# Sheet2.net
KiCad netlist of a schematic drawn in Altium Designer
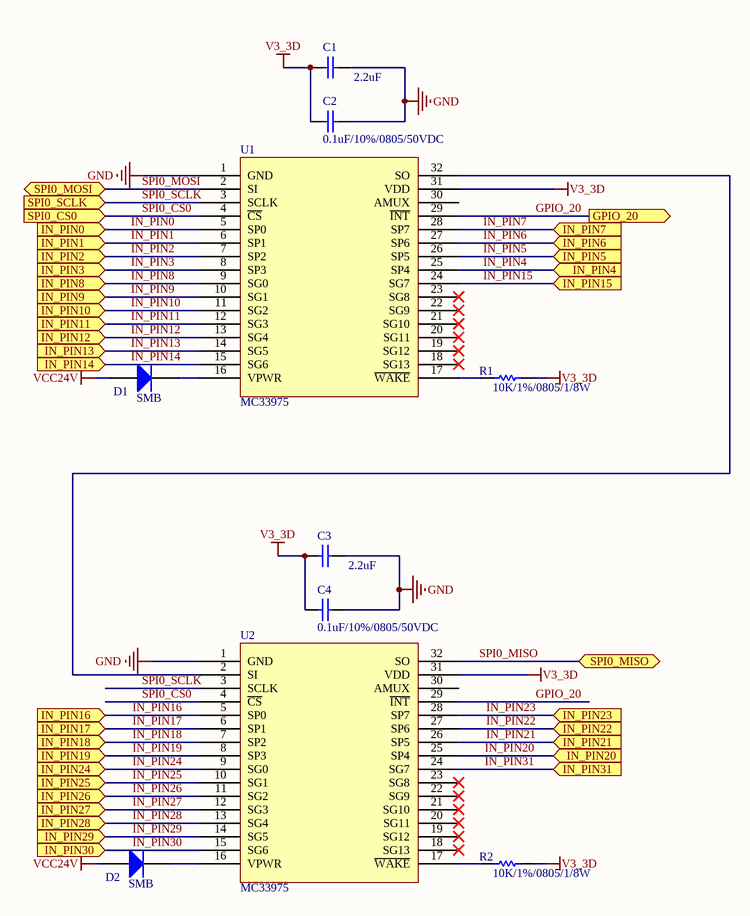
[diagram p0: Sheet2.SchDoc]

(export (version "E")
  (design (tool "Eeschema 10.0.6"))
  (components
    (comp (ref "C1")
      (value "2.2uF")
      (footprint "0805_cap")
      (description "Capacitor")
      (fields (field (name "PUBLISHER") "Altium Limited"))
      (libsource (lib "Miscellaneous Devices") (part "Cap"))
    )
    (comp (ref "C2")
      (value "0.1uF/10%/0805/50VDC")
      (footprint "0805_cap")
      (libsource (lib "浙江关西电机数据库") (part "CAP_Non-polarity"))
    )
    (comp (ref "C3")
      (value "2.2uF")
      (footprint "0805_cap")
      (description "Capacitor")
      (fields (field (name "PUBLISHER") "Altium Limited"))
      (libsource (lib "Miscellaneous Devices") (part "Cap"))
    )
    (comp (ref "C4")
      (value "0.1uF/10%/0805/50VDC")
      (footprint "0805_cap")
      (libsource (lib "浙江关西电机数据库") (part "CAP_Non-polarity"))
    )
    (comp (ref "D1")
      (value "SMB")
      (footprint "SMB")
      (description "3 Amp Medium Power Silicon Rectifier Diode")
      (fields (field (name "PUBLISHER") "Altium Limited"))
      (libsource (lib "Miscellaneous Devices") (part "Diode 1N5408"))
    )
    (comp (ref "D2")
      (value "SMB")
      (footprint "SMB")
      (description "3 Amp Medium Power Silicon Rectifier Diode")
      (fields (field (name "PUBLISHER") "Altium Limited"))
      (libsource (lib "Miscellaneous Devices") (part "Diode 1N5408"))
    )
    (comp (ref "R1")
      (value "10K/1%/0805/1/8W")
      (footprint "0805")
      (fields (field (name "PART NUMBER") "ASR-0028BA"))
      (libsource (lib "浙江关西电机数据库") (part "RES_1"))
    )
    (comp (ref "R2")
      (value "10K/1%/0805/1/8W")
      (footprint "0805")
      (fields (field (name "PART NUMBER") "ASR-0028BA"))
      (libsource (lib "浙江关西电机数据库") (part "RES_1"))
    )
    (comp (ref "U1")
      (value "MC33975")
      (footprint "SOIC-32")
      (libsource (lib "SCHLIBRARIES") (part "MC33975"))
    )
    (comp (ref "U2")
      (value "MC33975")
      (footprint "SOIC-32")
      (libsource (lib "SCHLIBRARIES") (part "MC33975"))
    )
  )
  (nets
    (net (code "1") (name "/GPIO_20") (class "Default")
      (node (ref "U1") (pin "29") (pinfunction "~{INT}_29") (pintype "passive"))
      (node (ref "U2") (pin "29") (pinfunction "~{INT}_29") (pintype "passive"))
    )
    (net (code "2") (name "/IN_PIN0") (class "Default")
      (node (ref "U1") (pin "5") (pinfunction "SP0_5") (pintype "passive"))
    )
    (net (code "3") (name "/IN_PIN1") (class "Default")
      (node (ref "U1") (pin "6") (pinfunction "SP1_6") (pintype "passive"))
    )
    (net (code "4") (name "/IN_PIN2") (class "Default")
      (node (ref "U1") (pin "7") (pinfunction "SP2_7") (pintype "passive"))
    )
    (net (code "5") (name "/IN_PIN3") (class "Default")
      (node (ref "U1") (pin "8") (pinfunction "SP3_8") (pintype "passive"))
    )
    (net (code "6") (name "/IN_PIN4") (class "Default")
      (node (ref "U1") (pin "25") (pinfunction "SP4_25") (pintype "passive"))
    )
    (net (code "7") (name "/IN_PIN5") (class "Default")
      (node (ref "U1") (pin "26") (pinfunction "SP5_26") (pintype "passive"))
    )
    (net (code "8") (name "/IN_PIN6") (class "Default")
      (node (ref "U1") (pin "27") (pinfunction "SP6_27") (pintype "passive"))
    )
    (net (code "9") (name "/IN_PIN7") (class "Default")
      (node (ref "U1") (pin "28") (pinfunction "SP7_28") (pintype "passive"))
    )
    (net (code "10") (name "/IN_PIN8") (class "Default")
      (node (ref "U1") (pin "9") (pinfunction "SG0_9") (pintype "passive"))
    )
    (net (code "11") (name "/IN_PIN9") (class "Default")
      (node (ref "U1") (pin "10") (pinfunction "SG1_10") (pintype "passive"))
    )
    (net (code "12") (name "/IN_PIN10") (class "Default")
      (node (ref "U1") (pin "11") (pinfunction "SG2_11") (pintype "passive"))
    )
    (net (code "13") (name "/IN_PIN11") (class "Default")
      (node (ref "U1") (pin "12") (pinfunction "SG3_12") (pintype "passive"))
    )
    (net (code "14") (name "/IN_PIN12") (class "Default")
      (node (ref "U1") (pin "13") (pinfunction "SG4_13") (pintype "passive"))
    )
    (net (code "15") (name "/IN_PIN13") (class "Default")
      (node (ref "U1") (pin "14") (pinfunction "SG5_14") (pintype "passive"))
    )
    (net (code "16") (name "/IN_PIN14") (class "Default")
      (node (ref "U1") (pin "15") (pinfunction "SG6_15") (pintype "passive"))
    )
    (net (code "17") (name "/IN_PIN15") (class "Default")
      (node (ref "U1") (pin "24") (pinfunction "SG7_24") (pintype "passive"))
    )
    (net (code "18") (name "/IN_PIN16") (class "Default")
      (node (ref "U2") (pin "5") (pinfunction "SP0_5") (pintype "passive"))
    )
    (net (code "19") (name "/IN_PIN17") (class "Default")
      (node (ref "U2") (pin "6") (pinfunction "SP1_6") (pintype "passive"))
    )
    (net (code "20") (name "/IN_PIN18") (class "Default")
      (node (ref "U2") (pin "7") (pinfunction "SP2_7") (pintype "passive"))
    )
    (net (code "21") (name "/IN_PIN19") (class "Default")
      (node (ref "U2") (pin "8") (pinfunction "SP3_8") (pintype "passive"))
    )
    (net (code "22") (name "/IN_PIN20") (class "Default")
      (node (ref "U2") (pin "25") (pinfunction "SP4_25") (pintype "passive"))
    )
    (net (code "23") (name "/IN_PIN21") (class "Default")
      (node (ref "U2") (pin "26") (pinfunction "SP5_26") (pintype "passive"))
    )
    (net (code "24") (name "/IN_PIN22") (class "Default")
      (node (ref "U2") (pin "27") (pinfunction "SP6_27") (pintype "passive"))
    )
    (net (code "25") (name "/IN_PIN23") (class "Default")
      (node (ref "U2") (pin "28") (pinfunction "SP7_28") (pintype "passive"))
    )
    (net (code "26") (name "/IN_PIN24") (class "Default")
      (node (ref "U2") (pin "9") (pinfunction "SG0_9") (pintype "passive"))
    )
    (net (code "27") (name "/IN_PIN25") (class "Default")
      (node (ref "U2") (pin "10") (pinfunction "SG1_10") (pintype "passive"))
    )
    (net (code "28") (name "/IN_PIN26") (class "Default")
      (node (ref "U2") (pin "11") (pinfunction "SG2_11") (pintype "passive"))
    )
    (net (code "29") (name "/IN_PIN27") (class "Default")
      (node (ref "U2") (pin "12") (pinfunction "SG3_12") (pintype "passive"))
    )
    (net (code "30") (name "/IN_PIN28") (class "Default")
      (node (ref "U2") (pin "13") (pinfunction "SG4_13") (pintype "passive"))
    )
    (net (code "31") (name "/IN_PIN29") (class "Default")
      (node (ref "U2") (pin "14") (pinfunction "SG5_14") (pintype "passive"))
    )
    (net (code "32") (name "/IN_PIN30") (class "Default")
      (node (ref "U2") (pin "15") (pinfunction "SG6_15") (pintype "passive"))
    )
    (net (code "33") (name "/IN_PIN31") (class "Default")
      (node (ref "U2") (pin "24") (pinfunction "SG7_24") (pintype "passive"))
    )
    (net (code "34") (name "/SPI0_CS0") (class "Default")
      (node (ref "U1") (pin "4") (pinfunction "~{CS}_4") (pintype "passive"))
      (node (ref "U2") (pin "4") (pinfunction "~{CS}_4") (pintype "passive"))
    )
    (net (code "35") (name "/SPI0_MISO") (class "Default")
      (node (ref "U2") (pin "32") (pinfunction "SO_32") (pintype "passive"))
    )
    (net (code "36") (name "/SPI0_MOSI") (class "Default")
      (node (ref "U1") (pin "2") (pinfunction "SI_2") (pintype "passive"))
    )
    (net (code "37") (name "/SPI0_SCLK") (class "Default")
      (node (ref "U1") (pin "3") (pinfunction "SCLK_3") (pintype "passive"))
      (node (ref "U2") (pin "3") (pinfunction "SCLK_3") (pintype "passive"))
    )
    (net (code "38") (name "GND") (class "Default")
      (node (ref "C1") (pin "1") (pinfunction "1_1") (pintype "passive"))
      (node (ref "C2") (pin "1") (pinfunction "1_1") (pintype "passive"))
      (node (ref "C3") (pin "1") (pinfunction "1_1") (pintype "passive"))
      (node (ref "C4") (pin "1") (pinfunction "1_1") (pintype "passive"))
      (node (ref "U1") (pin "1") (pinfunction "GND_1") (pintype "passive"))
      (node (ref "U2") (pin "1") (pinfunction "GND_1") (pintype "passive"))
    )
    (net (code "39") (name "Net-(D1-K)") (class "Default")
      (node (ref "D1") (pin "2") (pinfunction "K_2") (pintype "passive"))
      (node (ref "U1") (pin "16") (pinfunction "VPWR_16") (pintype "passive"))
    )
    (net (code "40") (name "Net-(D2-K)") (class "Default")
      (node (ref "D2") (pin "2") (pinfunction "K_2") (pintype "passive"))
      (node (ref "U2") (pin "16") (pinfunction "VPWR_16") (pintype "passive"))
    )
    (net (code "41") (name "Net-(U1-SO)") (class "Default")
      (node (ref "U1") (pin "32") (pinfunction "SO_32") (pintype "passive"))
      (node (ref "U2") (pin "2") (pinfunction "SI_2") (pintype "passive"))
    )
    (net (code "42") (name "Net-(U1-~{WAKE})") (class "Default")
      (node (ref "R1") (pin "2") (pinfunction "2_2") (pintype "passive"))
      (node (ref "U1") (pin "17") (pinfunction "~{WAKE}_17") (pintype "passive"))
    )
    (net (code "43") (name "Net-(U2-~{WAKE})") (class "Default")
      (node (ref "R2") (pin "2") (pinfunction "2_2") (pintype "passive"))
      (node (ref "U2") (pin "17") (pinfunction "~{WAKE}_17") (pintype "passive"))
    )
    (net (code "44") (name "V3_3D") (class "Default")
      (node (ref "C1") (pin "2") (pinfunction "2_2") (pintype "passive"))
      (node (ref "C2") (pin "2") (pinfunction "2_2") (pintype "passive"))
      (node (ref "C3") (pin "2") (pinfunction "2_2") (pintype "passive"))
      (node (ref "C4") (pin "2") (pinfunction "2_2") (pintype "passive"))
      (node (ref "R1") (pin "1") (pinfunction "1_1") (pintype "passive"))
      (node (ref "R2") (pin "1") (pinfunction "1_1") (pintype "passive"))
      (node (ref "U1") (pin "31") (pinfunction "VDD_31") (pintype "passive"))
      (node (ref "U2") (pin "31") (pinfunction "VDD_31") (pintype "passive"))
    )
    (net (code "45") (name "VCC24V") (class "Default")
      (node (ref "D1") (pin "1") (pinfunction "A_1") (pintype "passive"))
      (node (ref "D2") (pin "1") (pinfunction "A_1") (pintype "passive"))
    )
    (net (code "46") (name "unconnected-(U1-AMUX-Pad30)") (class "Default")
      (node (ref "U1") (pin "30") (pinfunction "AMUX_30") (pintype "passive"))
    )
    (net (code "47") (name "unconnected-(U1-SG8-Pad23)") (class "Default")
      (node (ref "U1") (pin "23") (pinfunction "SG8_23") (pintype "passive+no_connect"))
    )
    (net (code "48") (name "unconnected-(U1-SG9-Pad22)") (class "Default")
      (node (ref "U1") (pin "22") (pinfunction "SG9_22") (pintype "passive+no_connect"))
    )
    (net (code "49") (name "unconnected-(U1-SG10-Pad21)") (class "Default")
      (node (ref "U1") (pin "21") (pinfunction "SG10_21") (pintype "passive+no_connect"))
    )
    (net (code "50") (name "unconnected-(U1-SG11-Pad20)") (class "Default")
      (node (ref "U1") (pin "20") (pinfunction "SG11_20") (pintype "passive+no_connect"))
    )
    (net (code "51") (name "unconnected-(U1-SG12-Pad19)") (class "Default")
      (node (ref "U1") (pin "19") (pinfunction "SG12_19") (pintype "passive+no_connect"))
    )
    (net (code "52") (name "unconnected-(U1-SG13-Pad18)") (class "Default")
      (node (ref "U1") (pin "18") (pinfunction "SG13_18") (pintype "passive+no_connect"))
    )
    (net (code "53") (name "unconnected-(U2-AMUX-Pad30)") (class "Default")
      (node (ref "U2") (pin "30") (pinfunction "AMUX_30") (pintype "passive"))
    )
    (net (code "54") (name "unconnected-(U2-SG8-Pad23)") (class "Default")
      (node (ref "U2") (pin "23") (pinfunction "SG8_23") (pintype "passive+no_connect"))
    )
    (net (code "55") (name "unconnected-(U2-SG9-Pad22)") (class "Default")
      (node (ref "U2") (pin "22") (pinfunction "SG9_22") (pintype "passive+no_connect"))
    )
    (net (code "56") (name "unconnected-(U2-SG10-Pad21)") (class "Default")
      (node (ref "U2") (pin "21") (pinfunction "SG10_21") (pintype "passive+no_connect"))
    )
    (net (code "57") (name "unconnected-(U2-SG11-Pad20)") (class "Default")
      (node (ref "U2") (pin "20") (pinfunction "SG11_20") (pintype "passive+no_connect"))
    )
    (net (code "58") (name "unconnected-(U2-SG12-Pad19)") (class "Default")
      (node (ref "U2") (pin "19") (pinfunction "SG12_19") (pintype "passive+no_connect"))
    )
    (net (code "59") (name "unconnected-(U2-SG13-Pad18)") (class "Default")
      (node (ref "U2") (pin "18") (pinfunction "SG13_18") (pintype "passive+no_connect"))
    )
  )
)
